# Audio_stuff_CH.net
KiCad netlist of a schematic drawn in Altium Designer
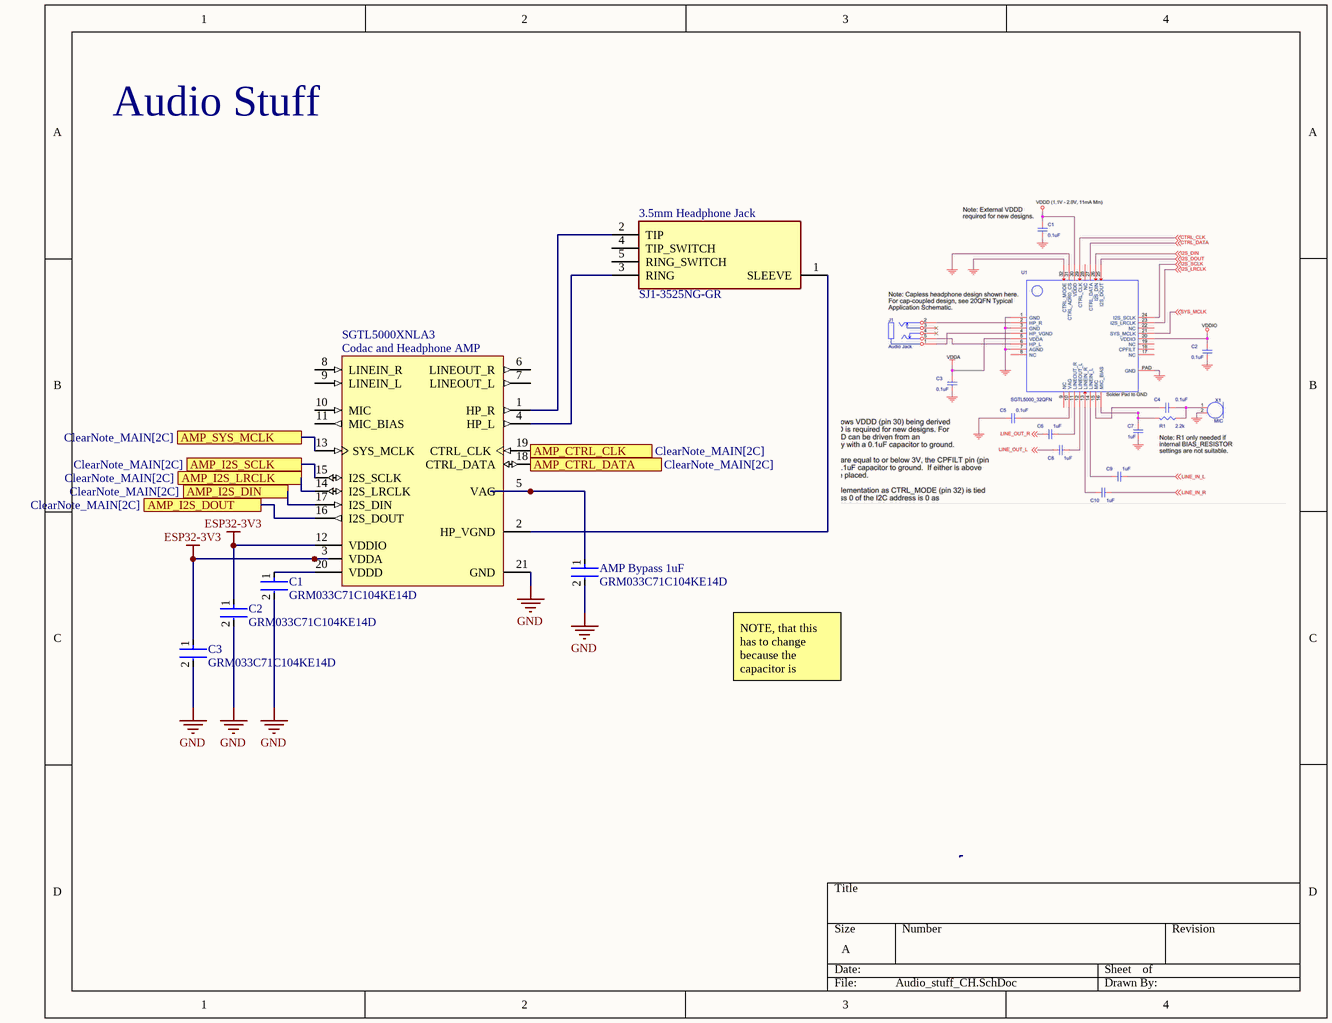
[diagram p0: Audio_stuff_CH.SchDoc]

(export (version "E")
  (design (tool "Eeschema 10.0.6"))
  (components
    (comp (ref "3.5mm Headphone Jack")
      (value "SJ1-3525NG-GR")
      (footprint "SamacSys:SJ13525NGGR")
      (description "Connector")
      (fields (field (name "MOUSER PART NUMBER") "490-SJ1-3525NG-GR"))
      (libsource (lib "SamacSys") (part "SJ1-3525NG-GR"))
    )
    (comp (ref "AMP Bypass 1uF")
      (value "GRM033C71C104KE14D")
      (footprint "FP-GRM033-0_03-MFG")
      (description "Chip Multilayer Ceramic Capacitors for General Purpose, 0201, 0.10uF, X7S, 22%, 10%, 16V")
      (fields (field (name "TOLERANCE") "10%"))
      (libsource (lib "Altium Content Vault") (part "b4654b650e69147ec39a6b967a45e02"))
    )
    (comp (ref "C1")
      (value "GRM033C71C104KE14D")
      (footprint "FP-GRM033-0_03-MFG")
      (description "Chip Multilayer Ceramic Capacitors for General Purpose, 0201, 0.10uF, X7S, 22%, 10%, 16V")
      (fields (field (name "TOLERANCE") "10%"))
      (libsource (lib "Altium Content Vault") (part "b4654b650e69147ec39a6b967a45e02"))
    )
    (comp (ref "C2")
      (value "GRM033C71C104KE14D")
      (footprint "FP-GRM033-0_03-MFG")
      (description "Chip Multilayer Ceramic Capacitors for General Purpose, 0201, 0.10uF, X7S, 22%, 10%, 16V")
      (fields (field (name "TOLERANCE") "10%"))
      (libsource (lib "Altium Content Vault") (part "b4654b650e69147ec39a6b967a45e02"))
    )
    (comp (ref "C3")
      (value "GRM033C71C104KE14D")
      (footprint "FP-GRM033-0_03-MFG")
      (description "Chip Multilayer Ceramic Capacitors for General Purpose, 0201, 0.10uF, X7S, 22%, 10%, 16V")
      (fields (field (name "TOLERANCE") "10%"))
      (libsource (lib "Altium Content Vault") (part "b4654b650e69147ec39a6b967a45e02"))
    )
    (comp (ref "Codac and Headphone AMP")
      (value "SGTL5000XNLA3")
      (footprint "FRES-2032-01_N")
      (description "Low Power Stereo Codec with Headphone Amp, 1.1 to 2 V, -40 to 85 degC, 20-Pin QFN-EP, RoHS, Tray")
      (fields (field (name "MANUFACTURER") "Freescale Semiconductor"))
      (libsource (lib "Altium Content Vault") (part "FRES-SGTL5000-20"))
    )
  )
  (nets
    (net (code "3") (name "/AMP_CTRL_CLK") (class "Default")
      (node (ref "Codac and Headphone AMP") (pin "19") (pinfunction "CTRL_CLK_19") (pintype "input"))
    )
    (net (code "4") (name "/AMP_CTRL_DATA") (class "Default")
      (node (ref "Codac and Headphone AMP") (pin "18") (pinfunction "CTRL_DATA_18") (pintype "bidirectional"))
    )
    (net (code "5") (name "/AMP_I2S_DIN") (class "Default")
      (node (ref "Codac and Headphone AMP") (pin "17") (pinfunction "I2S_DIN_17") (pintype "input"))
    )
    (net (code "6") (name "/AMP_I2S_DOUT") (class "Default")
      (node (ref "Codac and Headphone AMP") (pin "16") (pinfunction "I2S_DOUT_16") (pintype "output"))
    )
    (net (code "7") (name "/AMP_I2S_LRCLK") (class "Default")
      (node (ref "Codac and Headphone AMP") (pin "14") (pinfunction "I2S_LRCLK_14") (pintype "bidirectional"))
    )
    (net (code "8") (name "/AMP_I2S_SCLK") (class "Default")
      (node (ref "Codac and Headphone AMP") (pin "15") (pinfunction "I2S_SCLK_15") (pintype "bidirectional"))
    )
    (net (code "9") (name "/AMP_SYS_MCLK") (class "Default")
      (node (ref "Codac and Headphone AMP") (pin "13") (pinfunction "SYS_MCLK_13") (pintype "input"))
    )
    (net (code "10") (name "ESP32-3V3") (class "Default")
      (node (ref "C2") (pin "1") (pinfunction "1_1") (pintype "passive"))
      (node (ref "C3") (pin "1") (pinfunction "1_1") (pintype "passive"))
      (node (ref "Codac and Headphone AMP") (pin "12") (pinfunction "VDDIO_12") (pintype "power_in"))
      (node (ref "Codac and Headphone AMP") (pin "3") (pinfunction "VDDA_3") (pintype "power_in"))
    )
    (net (code "11") (name "GND") (class "Default")
      (node (ref "AMP Bypass 1uF") (pin "2") (pinfunction "2_2") (pintype "passive"))
      (node (ref "C1") (pin "2") (pinfunction "2_2") (pintype "passive"))
      (node (ref "C2") (pin "2") (pinfunction "2_2") (pintype "passive"))
      (node (ref "C3") (pin "2") (pinfunction "2_2") (pintype "passive"))
      (node (ref "Codac and Headphone AMP") (pin "21") (pinfunction "GND_21") (pintype "power_in"))
    )
    (net (code "12") (name "Net-(3.5mm Headphone Jack-RING)") (class "Default")
      (node (ref "3.5mm Headphone Jack") (pin "3") (pinfunction "RING_3") (pintype "passive"))
      (node (ref "Codac and Headphone AMP") (pin "4") (pinfunction "HP_L_4") (pintype "output"))
    )
    (net (code "13") (name "Net-(3.5mm Headphone Jack-SLEEVE)") (class "Default")
      (node (ref "3.5mm Headphone Jack") (pin "1") (pinfunction "SLEEVE_1") (pintype "passive"))
      (node (ref "Codac and Headphone AMP") (pin "2") (pinfunction "HP_VGND_2") (pintype "power_in"))
    )
    (net (code "14") (name "Net-(3.5mm Headphone Jack-TIP)") (class "Default")
      (node (ref "3.5mm Headphone Jack") (pin "2") (pinfunction "TIP_2") (pintype "passive"))
      (node (ref "Codac and Headphone AMP") (pin "1") (pinfunction "HP_R_1") (pintype "output"))
    )
    (net (code "15") (name "Net-(Codac and Headphone AMP-VAG)") (class "Default")
      (node (ref "AMP Bypass 1uF") (pin "1") (pinfunction "1_1") (pintype "passive"))
      (node (ref "Codac and Headphone AMP") (pin "5") (pinfunction "VAG_5") (pintype "passive"))
    )
    (net (code "16") (name "Net-(Codac and Headphone AMP-VDDD)") (class "Default")
      (node (ref "C1") (pin "1") (pinfunction "1_1") (pintype "passive"))
      (node (ref "Codac and Headphone AMP") (pin "20") (pinfunction "VDDD_20") (pintype "power_in"))
    )
    (net (code "17") (name "unconnected-(3.5mm Headphone Jack-RING_SWITCH-Pad5)") (class "Default")
      (node (ref "3.5mm Headphone Jack") (pin "5") (pinfunction "RING_SWITCH_5") (pintype "passive"))
    )
    (net (code "18") (name "unconnected-(3.5mm Headphone Jack-TIP_SWITCH-Pad4)") (class "Default")
      (node (ref "3.5mm Headphone Jack") (pin "4") (pinfunction "TIP_SWITCH_4") (pintype "passive"))
    )
    (net (code "19") (name "unconnected-(Codac and Headphone AMP-LINEIN_L-Pad9)") (class "Default")
      (node (ref "Codac and Headphone AMP") (pin "9") (pinfunction "LINEIN_L_9") (pintype "input"))
    )
    (net (code "20") (name "unconnected-(Codac and Headphone AMP-LINEIN_R-Pad8)") (class "Default")
      (node (ref "Codac and Headphone AMP") (pin "8") (pinfunction "LINEIN_R_8") (pintype "input"))
    )
    (net (code "21") (name "unconnected-(Codac and Headphone AMP-LINEOUT_L-Pad7)") (class "Default")
      (node (ref "Codac and Headphone AMP") (pin "7") (pinfunction "LINEOUT_L_7") (pintype "output"))
    )
    (net (code "22") (name "unconnected-(Codac and Headphone AMP-LINEOUT_R-Pad6)") (class "Default")
      (node (ref "Codac and Headphone AMP") (pin "6") (pinfunction "LINEOUT_R_6") (pintype "output"))
    )
    (net (code "23") (name "unconnected-(Codac and Headphone AMP-MIC-Pad10)") (class "Default")
      (node (ref "Codac and Headphone AMP") (pin "10") (pinfunction "MIC_10") (pintype "input"))
    )
    (net (code "24") (name "unconnected-(Codac and Headphone AMP-MIC_BIAS-Pad11)") (class "Default")
      (node (ref "Codac and Headphone AMP") (pin "11") (pinfunction "MIC_BIAS_11") (pintype "output"))
    )
  )
)
